# counter_shield.net
KiCad netlist of a schematic drawn in EAGLE
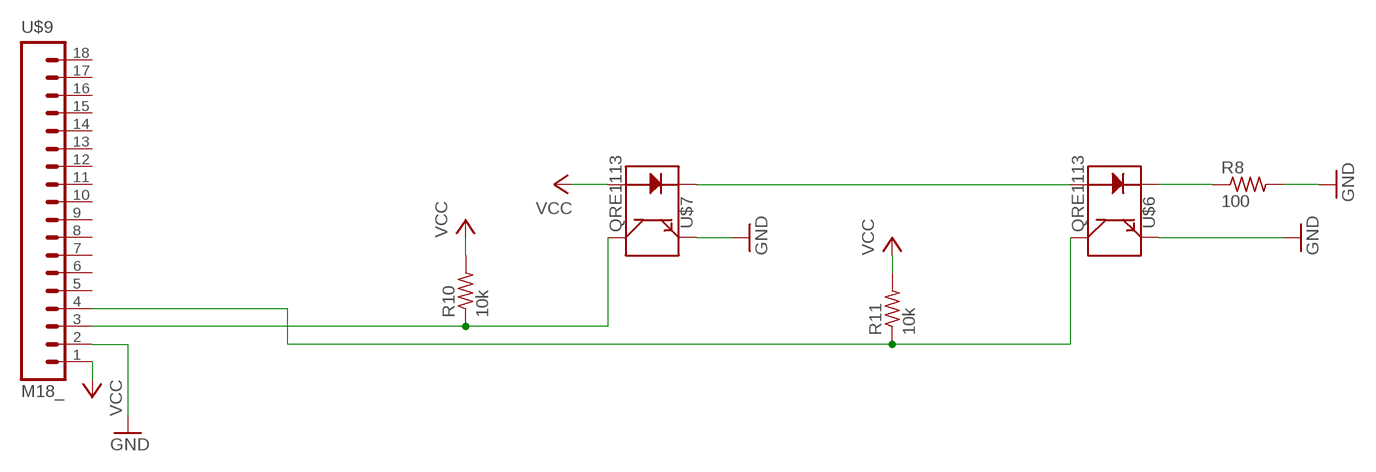
[diagram p0: schematic, sheet 1]

(export (version "E")
  (design (tool "Eeschema 10.0.6"))
  (components
    (comp (ref "R8")
      (value "100")
      (footprint "eagle-import:1206")
      (libsource (lib "eagle-import") (part "RESISTOR1206"))
    )
    (comp (ref "R10")
      (value "10k")
      (footprint "eagle-import:1206")
      (libsource (lib "eagle-import") (part "RESISTOR1206"))
    )
    (comp (ref "R11")
      (value "10k")
      (footprint "eagle-import:1206")
      (libsource (lib "eagle-import") (part "RESISTOR1206"))
    )
    (comp (ref "U$6")
      (value "QRE1113")
      (footprint "eagle-import:QRE1113")
      (libsource (lib "eagle-import") (part "QRE1113"))
    )
    (comp (ref "U$7")
      (value "QRE1113")
      (footprint "eagle-import:QRE1113")
      (libsource (lib "eagle-import") (part "QRE1113"))
    )
    (comp (ref "U$9")
      (value "M18_")
      (footprint "eagle-import:1X18")
      (libsource (lib "eagle-import") (part "M18_"))
    )
  )
  (nets
    (net (code "1") (name "GND") (class "Default")
      (node (ref "R8") (pin "2") (pinfunction "2_2") (pintype "passive"))
      (node (ref "U$6") (pin "4") (pinfunction "E_4") (pintype "bidirectional"))
      (node (ref "U$7") (pin "4") (pinfunction "E_4") (pintype "bidirectional"))
      (node (ref "U$9") (pin "2") (pinfunction "2_2") (pintype "passive"))
    )
    (net (code "2") (name "Net-(U$6-A)") (class "Default")
      (node (ref "U$6") (pin "1") (pinfunction "A_1") (pintype "bidirectional"))
      (node (ref "U$7") (pin "2") (pinfunction "K_2") (pintype "bidirectional"))
    )
    (net (code "3") (name "Net-(U$6-C)") (class "Default")
      (node (ref "R11") (pin "1") (pinfunction "1_1") (pintype "passive"))
      (node (ref "U$6") (pin "3") (pinfunction "C_3") (pintype "bidirectional"))
      (node (ref "U$9") (pin "4") (pinfunction "4_4") (pintype "passive"))
    )
    (net (code "4") (name "Net-(U$6-K)") (class "Default")
      (node (ref "R8") (pin "1") (pinfunction "1_1") (pintype "passive"))
      (node (ref "U$6") (pin "2") (pinfunction "K_2") (pintype "bidirectional"))
    )
    (net (code "5") (name "Net-(U$7-C)") (class "Default")
      (node (ref "R10") (pin "1") (pinfunction "1_1") (pintype "passive"))
      (node (ref "U$7") (pin "3") (pinfunction "C_3") (pintype "bidirectional"))
      (node (ref "U$9") (pin "3") (pinfunction "3_3") (pintype "passive"))
    )
    (net (code "6") (name "VCC") (class "Default")
      (node (ref "R10") (pin "2") (pinfunction "2_2") (pintype "passive"))
      (node (ref "R11") (pin "2") (pinfunction "2_2") (pintype "passive"))
      (node (ref "U$7") (pin "1") (pinfunction "A_1") (pintype "bidirectional"))
      (node (ref "U$9") (pin "1") (pinfunction "1_1") (pintype "passive"))
    )
    (net (code "7") (name "unconnected-(U$9-Pad5)") (class "Default")
      (node (ref "U$9") (pin "5") (pinfunction "5_5") (pintype "passive"))
    )
    (net (code "8") (name "unconnected-(U$9-Pad6)") (class "Default")
      (node (ref "U$9") (pin "6") (pinfunction "6_6") (pintype "passive"))
    )
    (net (code "9") (name "unconnected-(U$9-Pad7)") (class "Default")
      (node (ref "U$9") (pin "7") (pinfunction "7_7") (pintype "passive"))
    )
    (net (code "10") (name "unconnected-(U$9-Pad8)") (class "Default")
      (node (ref "U$9") (pin "8") (pinfunction "8_8") (pintype "passive"))
    )
    (net (code "11") (name "unconnected-(U$9-Pad9)") (class "Default")
      (node (ref "U$9") (pin "9") (pinfunction "9_9") (pintype "passive"))
    )
    (net (code "12") (name "unconnected-(U$9-Pad10)") (class "Default")
      (node (ref "U$9") (pin "10") (pinfunction "10_10") (pintype "passive"))
    )
    (net (code "13") (name "unconnected-(U$9-Pad11)") (class "Default")
      (node (ref "U$9") (pin "11") (pinfunction "11_11") (pintype "passive"))
    )
    (net (code "14") (name "unconnected-(U$9-Pad12)") (class "Default")
      (node (ref "U$9") (pin "12") (pinfunction "12_12") (pintype "passive"))
    )
    (net (code "15") (name "unconnected-(U$9-Pad13)") (class "Default")
      (node (ref "U$9") (pin "13") (pinfunction "13_13") (pintype "passive"))
    )
    (net (code "16") (name "unconnected-(U$9-Pad14)") (class "Default")
      (node (ref "U$9") (pin "14") (pinfunction "14_14") (pintype "passive"))
    )
    (net (code "17") (name "unconnected-(U$9-Pad15)") (class "Default")
      (node (ref "U$9") (pin "15") (pinfunction "15_15") (pintype "passive"))
    )
    (net (code "18") (name "unconnected-(U$9-Pad16)") (class "Default")
      (node (ref "U$9") (pin "16") (pinfunction "16_16") (pintype "passive"))
    )
    (net (code "19") (name "unconnected-(U$9-Pad17)") (class "Default")
      (node (ref "U$9") (pin "17") (pinfunction "17_17") (pintype "passive"))
    )
    (net (code "20") (name "unconnected-(U$9-Pad18)") (class "Default")
      (node (ref "U$9") (pin "18") (pinfunction "18_18") (pintype "passive"))
    )
  )
)
